# Shutdown_2019_v1_1_7.net
KiCad netlist of a schematic drawn in Altium Designer
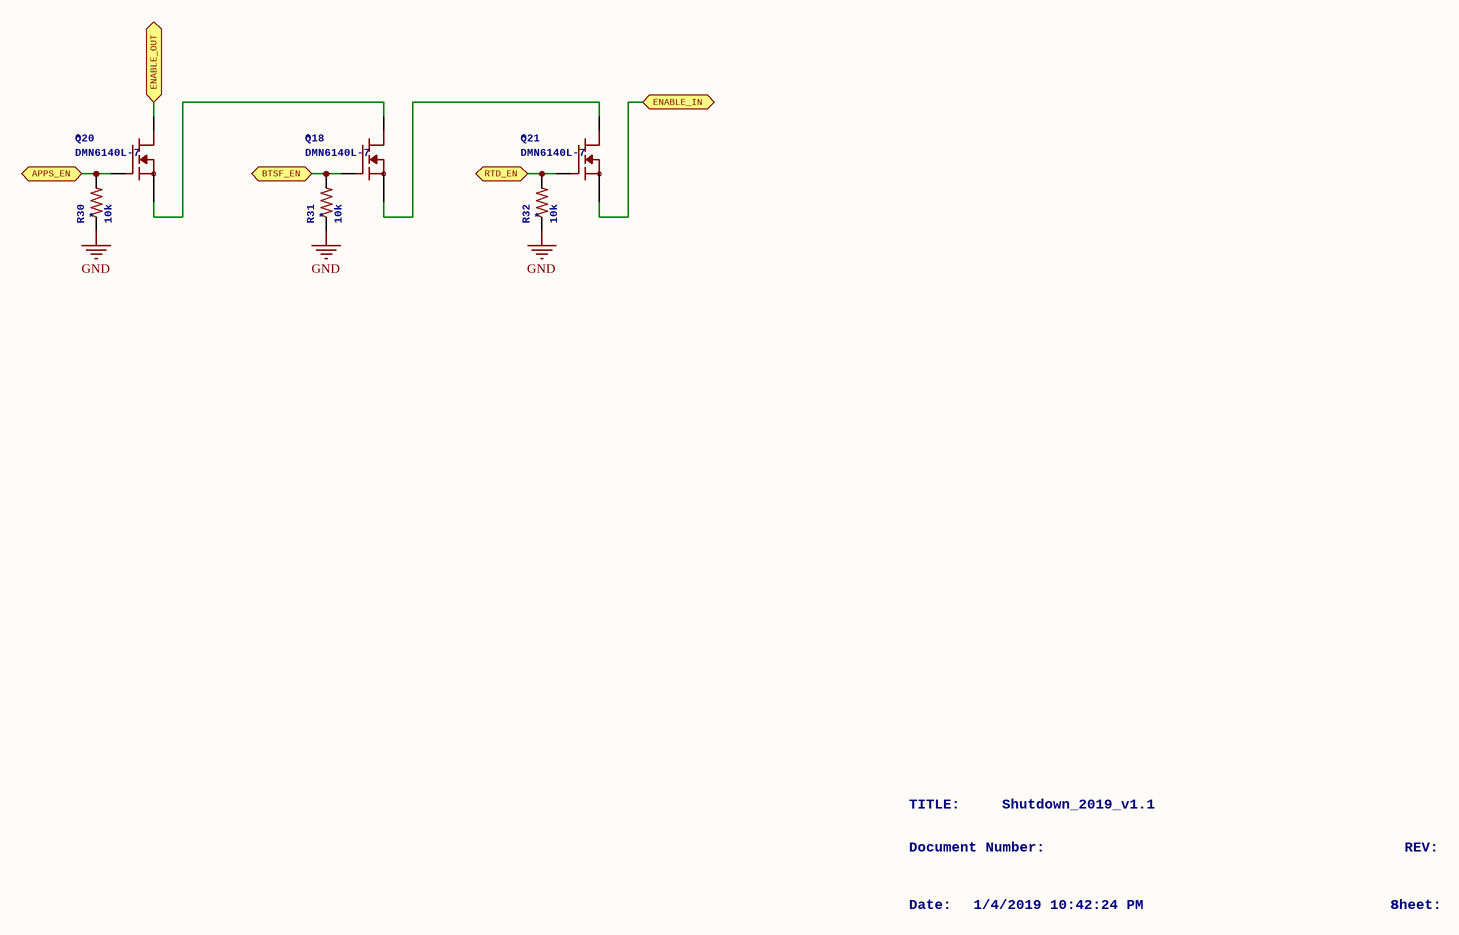
[diagram p0: Shutdown_2019_v1.1_7.SchDoc]

(export (version "E")
  (design (tool "Eeschema 10.0.6"))
  (components
    (comp (ref "Q18")
      (value "DMN6140L-7")
      (footprint "SOT23")
      (description "DMN6140L-7 Vgs(th) = 3V, Rds(on) = 140mOhm, Vds(max) = 60V")
      (fields (field (name "NAME") "*"))
      (libsource (lib "TRANS") (part "DMN6140L-7"))
    )
    (comp (ref "Q20")
      (value "DMN6140L-7")
      (footprint "SOT23")
      (description "DMN6140L-7 Vgs(th) = 3V, Rds(on) = 140mOhm, Vds(max) = 60V")
      (fields (field (name "NAME") "*"))
      (libsource (lib "TRANS") (part "DMN6140L-7"))
    )
    (comp (ref "Q21")
      (value "DMN6140L-7")
      (footprint "SOT23")
      (description "DMN6140L-7 Vgs(th) = 3V, Rds(on) = 140mOhm, Vds(max) = 60V")
      (fields (field (name "NAME") "*"))
      (libsource (lib "TRANS") (part "DMN6140L-7"))
    )
    (comp (ref "R30")
      (value "10k")
      (footprint "R0603")
      (description "RESISTOR, American symbol")
      (fields (field (name "NAME") "*"))
      (libsource (lib "rcl") (part "R-US_R0603"))
    )
    (comp (ref "R31")
      (value "10k")
      (footprint "R0603")
      (description "RESISTOR, American symbol")
      (fields (field (name "NAME") "*"))
      (libsource (lib "rcl") (part "R-US_R0603"))
    )
    (comp (ref "R32")
      (value "10k")
      (footprint "R0603")
      (description "RESISTOR, American symbol")
      (fields (field (name "NAME") "*"))
      (libsource (lib "rcl") (part "R-US_R0603"))
    )
  )
  (nets
    (net (code "1") (name "/APPS_EN") (class "Default")
      (node (ref "Q20") (pin "1") (pinfunction "G_1") (pintype "passive"))
      (node (ref "R30") (pin "2") (pinfunction "2_2") (pintype "passive"))
    )
    (net (code "2") (name "/BTSF_EN") (class "Default")
      (node (ref "Q18") (pin "1") (pinfunction "G_1") (pintype "passive"))
      (node (ref "R31") (pin "2") (pinfunction "2_2") (pintype "passive"))
    )
    (net (code "3") (name "/ENABLE_IN") (class "Default")
      (node (ref "Q21") (pin "2") (pinfunction "S_2") (pintype "passive"))
    )
    (net (code "4") (name "/ENABLE_OUT") (class "Default")
      (node (ref "Q20") (pin "3") (pinfunction "D_3") (pintype "passive"))
    )
    (net (code "5") (name "/RTD_EN") (class "Default")
      (node (ref "Q21") (pin "1") (pinfunction "G_1") (pintype "passive"))
      (node (ref "R32") (pin "2") (pinfunction "2_2") (pintype "passive"))
    )
    (net (code "6") (name "GND") (class "Default")
      (node (ref "R30") (pin "1") (pinfunction "1_1") (pintype "passive"))
      (node (ref "R31") (pin "1") (pinfunction "1_1") (pintype "passive"))
      (node (ref "R32") (pin "1") (pinfunction "1_1") (pintype "passive"))
    )
    (net (code "7") (name "Net-(Q18-D)") (class "Default")
      (node (ref "Q18") (pin "3") (pinfunction "D_3") (pintype "passive"))
      (node (ref "Q20") (pin "2") (pinfunction "S_2") (pintype "passive"))
    )
    (net (code "8") (name "Net-(Q18-S)") (class "Default")
      (node (ref "Q18") (pin "2") (pinfunction "S_2") (pintype "passive"))
      (node (ref "Q21") (pin "3") (pinfunction "D_3") (pintype "passive"))
    )
  )
)
